# power.net
KiCad netlist of a schematic drawn in Altium Designer
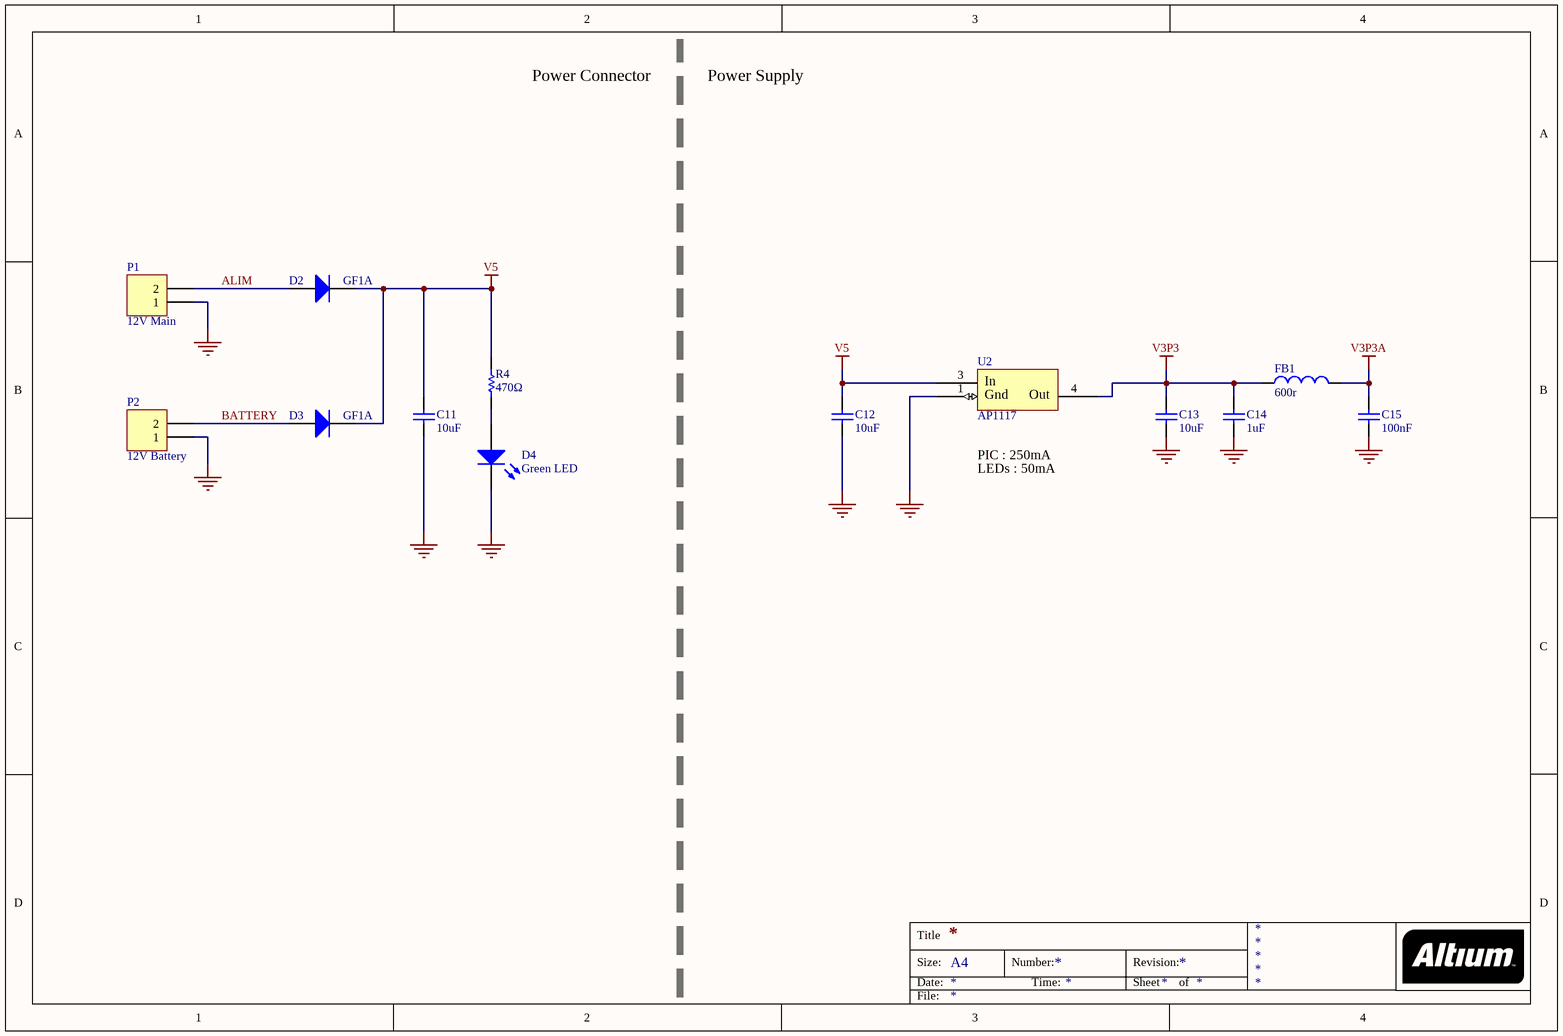
[diagram p0: power.SchDoc]

(export (version "E")
  (design (tool "Eeschema 10.0.6"))
  (components
    (comp (ref "C11")
      (value "10uF")
      (footprint "CAPC2012N")
      (description "Capacitor")
      (fields (field (name "PUBLISHER") "Altium Limited"))
      (libsource (lib "Miscellaneous Devices") (part "Cap"))
    )
    (comp (ref "C12")
      (value "10uF")
      (footprint "CAPC2012N")
      (description "Capacitor")
      (fields (field (name "PUBLISHER") "Altium Limited"))
      (libsource (lib "Miscellaneous Devices") (part "Cap"))
    )
    (comp (ref "C13")
      (value "10uF")
      (footprint "CAPC2012N")
      (description "Capacitor")
      (fields (field (name "PUBLISHER") "Altium Limited"))
      (libsource (lib "Miscellaneous Devices") (part "Cap"))
    )
    (comp (ref "C14")
      (value "1uF")
      (footprint "CAPC1608N")
      (description "Capacitor")
      (fields (field (name "PUBLISHER") "Altium Limited"))
      (libsource (lib "Miscellaneous Devices") (part "Cap"))
    )
    (comp (ref "C15")
      (value "100nF")
      (footprint "CAPC1608N")
      (description "Capacitor")
      (fields (field (name "PUBLISHER") "Altium Limited"))
      (libsource (lib "Miscellaneous Devices") (part "Cap"))
    )
    (comp (ref "D2")
      (value "GF1A")
      (footprint "SMA/DO-214AC")
      (description "Default Diode")
      (fields (field (name "PUBLISHER") "Altium Limited"))
      (libsource (lib "Miscellaneous Devices") (part "Diode"))
    )
    (comp (ref "D3")
      (value "GF1A")
      (footprint "SMA/DO-214AC")
      (description "Default Diode")
      (fields (field (name "PUBLISHER") "Altium Limited"))
      (libsource (lib "Miscellaneous Devices") (part "Diode"))
    )
    (comp (ref "D4")
      (value "Green LED")
      (footprint "LED 0805")
      (description "Typical INFRARED GaAs LED")
      (fields (field (name "PUBLISHER") "Altium Limited"))
      (libsource (lib "Miscellaneous Devices") (part "LED0"))
    )
    (comp (ref "FB1")
      (value "600r")
      (footprint "INDC1608AN")
      (description "Inductor")
      (fields (field (name "PUBLISHER") "Altium Limited"))
      (libsource (lib "Miscellaneous Devices") (part "Inductor"))
    )
    (comp (ref "P1")
      (value "12V Main")
      (footprint "PHOENIX_1985195")
      (description "Header, 2-Pin")
      (fields (field (name "PUBLISHER") "Altium Limited"))
      (libsource (lib "Miscellaneous Connectors") (part "Header 2"))
    )
    (comp (ref "P2")
      (value "12V Battery")
      (footprint "PHOENIX_1985195")
      (description "Header, 2-Pin")
      (fields (field (name "PUBLISHER") "Altium Limited"))
      (libsource (lib "Miscellaneous Connectors") (part "Header 2"))
    )
    (comp (ref "R4")
      (value "470Ω")
      (footprint "RESC1608N")
      (description "Resistor")
      (fields (field (name "PUBLISHER") "Altium Limited"))
      (libsource (lib "Miscellaneous Devices") (part "Res1"))
    )
    (comp (ref "U2")
      (value "AP1117")
      (footprint "TD03B_N")
      (description "1A LDO, 18V input, DPAK")
      (libsource (lib "TP2lib") (part "AP1117"))
    )
  )
  (nets
    (net (code "1") (name "/ALIM") (class "Default")
      (node (ref "D2") (pin "1") (pinfunction "A_1") (pintype "passive"))
      (node (ref "P1") (pin "2") (pinfunction "2_2") (pintype "passive"))
    )
    (net (code "2") (name "/BATTERY") (class "Default")
      (node (ref "D3") (pin "1") (pinfunction "A_1") (pintype "passive"))
      (node (ref "P2") (pin "2") (pinfunction "2_2") (pintype "passive"))
    )
    (net (code "3") (name "GND") (class "Default")
      (node (ref "C11") (pin "1") (pinfunction "1_1") (pintype "passive"))
      (node (ref "C12") (pin "1") (pinfunction "1_1") (pintype "passive"))
      (node (ref "C13") (pin "1") (pinfunction "1_1") (pintype "passive"))
      (node (ref "C14") (pin "1") (pinfunction "1_1") (pintype "passive"))
      (node (ref "C15") (pin "1") (pinfunction "1_1") (pintype "passive"))
      (node (ref "D4") (pin "2") (pinfunction "K_2") (pintype "passive"))
      (node (ref "P1") (pin "1") (pinfunction "1_1") (pintype "passive"))
      (node (ref "P2") (pin "1") (pinfunction "1_1") (pintype "passive"))
      (node (ref "U2") (pin "1") (pinfunction "1_1") (pintype "bidirectional"))
    )
    (net (code "4") (name "Net-(D4-A)") (class "Default")
      (node (ref "D4") (pin "1") (pinfunction "A_1") (pintype "passive"))
      (node (ref "R4") (pin "1") (pinfunction "1_1") (pintype "passive"))
    )
    (net (code "5") (name "V3P3") (class "Default")
      (node (ref "C13") (pin "2") (pinfunction "2_2") (pintype "passive"))
      (node (ref "C14") (pin "2") (pinfunction "2_2") (pintype "passive"))
      (node (ref "FB1") (pin "1") (pinfunction "1_1") (pintype "passive"))
      (node (ref "U2") (pin "4") (pinfunction "4_4") (pintype "power_in"))
    )
    (net (code "6") (name "V3P3A") (class "Default")
      (node (ref "C15") (pin "2") (pinfunction "2_2") (pintype "passive"))
      (node (ref "FB1") (pin "2") (pinfunction "2_2") (pintype "passive"))
    )
    (net (code "7") (name "V5") (class "Default")
      (node (ref "C11") (pin "2") (pinfunction "2_2") (pintype "passive"))
      (node (ref "C12") (pin "2") (pinfunction "2_2") (pintype "passive"))
      (node (ref "D2") (pin "2") (pinfunction "K_2") (pintype "passive"))
      (node (ref "D3") (pin "2") (pinfunction "K_2") (pintype "passive"))
      (node (ref "R4") (pin "2") (pinfunction "2_2") (pintype "passive"))
      (node (ref "U2") (pin "3") (pinfunction "3_3") (pintype "power_in"))
    )
  )
)
